# OMD_CAN_HORIZONTAL.net
KiCad netlist of a schematic drawn in Altium Designer
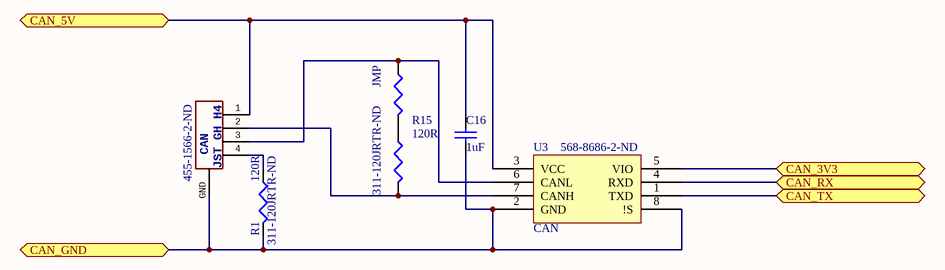
[diagram p0: OMD_CAN_HORIZONTAL.SchDoc]

(export (version "E")
  (design (tool "Eeschema 10.0.6"))
  (components
    (comp (ref "C16")
      (value "1uF")
      (footprint "CAPC1005L")
      (description "CAP CER 1UF 6.3V X5R 0402")
      (fields (field (name "Comment") "Cap"))
      (libsource (lib "OMD") (part "Cap"))
    )
    (comp (ref "CAN")
      (value "JST_GH_H4")
      (footprint "JST_GH_H4")
      (description "SM04B-GHS-TB")
      (fields (field (name "SUPPLIER PART NUMBER 1") "455-1566-2-ND"))
      (libsource (lib "OMD") (part "JST_GH_H4"))
    )
    (comp (ref "JMP") (value "solder") (footprint "R0402") (libsource (lib "OMD") (part "Resistor")))
    (comp (ref "R1")
      (value "120R")
      (footprint "R0402")
      (description "RES SMD 120 OHM 5% 1/16W 0402")
      (fields (field (name "SUPPLIER PART NUMBER 1") "311-120JRTR-ND"))
      (libsource (lib "OMD") (part "Resistor"))
    )
    (comp (ref "R15")
      (value "120R")
      (footprint "R0402")
      (description "RES SMD 120 OHM 5% 1/16W 0402")
      (fields (field (name "SUPPLIER PART NUMBER 1") "311-120JRTR-ND"))
      (libsource (lib "OMD") (part "Resistor"))
    )
    (comp (ref "U3")
      (value "CAN")
      (footprint "SON65P300X100_HS-9N")
      (fields (field (name "SUPPLIER PART NUMBER 1") "568-8686-2-ND"))
      (libsource (lib "OMD") (part "CAN"))
    )
  )
  (nets
    (net (code "1") (name "/CAN_3V3") (class "Default")
      (node (ref "U3") (pin "5") (pinfunction "VIO_5") (pintype "passive"))
    )
    (net (code "2") (name "/CAN_5V") (class "Default")
      (node (ref "C16") (pin "2") (pinfunction "2_2") (pintype "passive"))
      (node (ref "CAN") (pin "1") (pinfunction "1_1") (pintype "passive"))
      (node (ref "U3") (pin "3") (pinfunction "VCC_3") (pintype "passive"))
    )
    (net (code "3") (name "/CAN_GND") (class "Default")
      (node (ref "C16") (pin "1") (pinfunction "1_1") (pintype "passive"))
      (node (ref "CAN") (pin "GND") (pinfunction "GND_GND") (pintype "passive"))
      (node (ref "R1") (pin "2") (pinfunction "2_2") (pintype "passive"))
      (node (ref "U3") (pin "2") (pinfunction "GND_2") (pintype "passive"))
      (node (ref "U3") (pin "8") (pinfunction "!S_8") (pintype "passive"))
    )
    (net (code "4") (name "/CAN_RX") (class "Default")
      (node (ref "U3") (pin "4") (pinfunction "RXD_4") (pintype "passive"))
    )
    (net (code "5") (name "/CAN_TX") (class "Default")
      (node (ref "U3") (pin "1") (pinfunction "TXD_1") (pintype "passive"))
    )
    (net (code "6") (name "Net-(CAN-Pad4)") (class "Default")
      (node (ref "CAN") (pin "4") (pinfunction "4_4") (pintype "passive"))
      (node (ref "R1") (pin "1") (pinfunction "1_1") (pintype "passive"))
    )
    (net (code "7") (name "Net-(JMP-Pad2)") (class "Default")
      (node (ref "JMP") (pin "2") (pinfunction "2_2") (pintype "passive"))
      (node (ref "R15") (pin "1") (pinfunction "1_1") (pintype "passive"))
    )
    (net (code "8") (name "Net-(U3-CANH)") (class "Default")
      (node (ref "CAN") (pin "2") (pinfunction "2_2") (pintype "passive"))
      (node (ref "R15") (pin "2") (pinfunction "2_2") (pintype "passive"))
      (node (ref "U3") (pin "7") (pinfunction "CANH_7") (pintype "passive"))
    )
    (net (code "9") (name "Net-(U3-CANL)") (class "Default")
      (node (ref "CAN") (pin "3") (pinfunction "3_3") (pintype "passive"))
      (node (ref "JMP") (pin "1") (pinfunction "1_1") (pintype "passive"))
      (node (ref "U3") (pin "6") (pinfunction "CANL_6") (pintype "passive"))
    )
  )
)
